# max1k.net
KiCad netlist of a schematic drawn in EAGLE
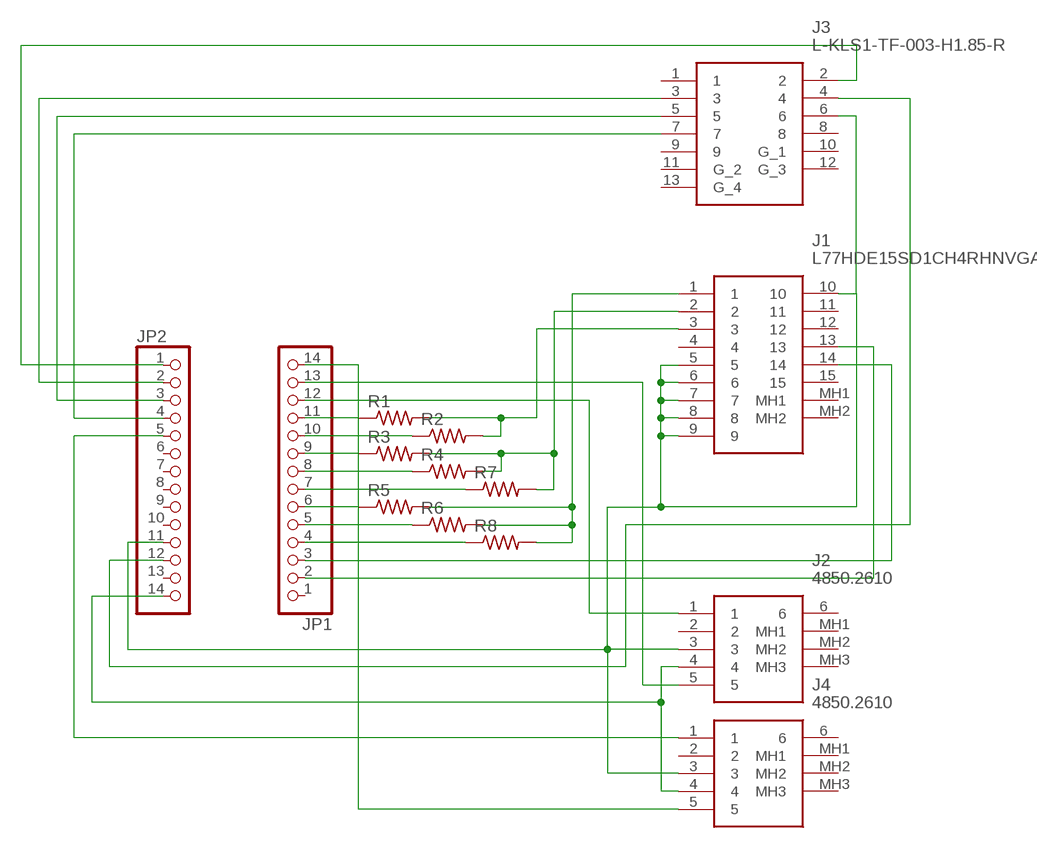
[diagram p0: schematic, sheet 1]

(export (version "E")
  (design (tool "Eeschema 10.0.6"))
  (components
    (comp (ref "J1")
      (value "L77HDE15SD1CH4RHNVGA")
      (footprint "eagle-import:L77HDE15SD1CH4RHNVGA")
      (fields (field (name "MOUSER_PART_NUMBER") "523-7HDE15SDH4RHNVGA"))
      (libsource (lib "eagle-import") (part "L77HDE15SD1CH4RHNVGA"))
    )
    (comp (ref "J2")
      (value "4850.2610")
      (footprint "eagle-import:48502610")
      (fields (field (name "MOUSER_PART_NUMBER") "693-4850.2610"))
      (libsource (lib "eagle-import") (part "4850.2610"))
    )
    (comp (ref "J3")
      (value "L-KLS1-TF-003-H1.85-R")
      (footprint "eagle-import:L-KLS1-TF-003-H1.85-R")
      (libsource (lib "eagle-import") (part "L-KLS1-TF-003-H1.85-R"))
    )
    (comp (ref "J4")
      (value "4850.2610")
      (footprint "eagle-import:48502610")
      (fields (field (name "MOUSER_PART_NUMBER") "693-4850.2610"))
      (libsource (lib "eagle-import") (part "4850.2610"))
    )
    (comp (ref "JP1")
      (value "PINHD-1X14-CB")
      (footprint "eagle-import:1X14-CB")
      (libsource (lib "eagle-import") (part "PINHD-1X14-CB"))
    )
    (comp (ref "JP2")
      (value "PINHD-1X14-CB")
      (footprint "eagle-import:1X14-CB")
      (libsource (lib "eagle-import") (part "PINHD-1X14-CB"))
    )
    (comp (ref "R1")
      (value "R-US_R0805")
      (footprint "eagle-import:R0805")
      (libsource (lib "eagle-import") (part "R-US_R0805"))
    )
    (comp (ref "R2")
      (value "R-US_R0805")
      (footprint "eagle-import:R0805")
      (libsource (lib "eagle-import") (part "R-US_R0805"))
    )
    (comp (ref "R3")
      (value "R-US_R0805")
      (footprint "eagle-import:R0805")
      (libsource (lib "eagle-import") (part "R-US_R0805"))
    )
    (comp (ref "R4")
      (value "R-US_R0805")
      (footprint "eagle-import:R0805")
      (libsource (lib "eagle-import") (part "R-US_R0805"))
    )
    (comp (ref "R5")
      (value "R-US_R0805")
      (footprint "eagle-import:R0805")
      (libsource (lib "eagle-import") (part "R-US_R0805"))
    )
    (comp (ref "R6")
      (value "R-US_R0805")
      (footprint "eagle-import:R0805")
      (libsource (lib "eagle-import") (part "R-US_R0805"))
    )
    (comp (ref "R7")
      (value "R-US_R0805")
      (footprint "eagle-import:R0805")
      (libsource (lib "eagle-import") (part "R-US_R0805"))
    )
    (comp (ref "R8")
      (value "R-US_R0805")
      (footprint "eagle-import:R0805")
      (libsource (lib "eagle-import") (part "R-US_R0805"))
    )
  )
  (nets
    (net (code "1") (name "Net-(J1-Pad1)") (class "Default")
      (node (ref "J1") (pin "1") (pinfunction "1_1") (pintype "bidirectional"))
      (node (ref "R5") (pin "2") (pinfunction "2_2") (pintype "passive"))
      (node (ref "R6") (pin "2") (pinfunction "2_2") (pintype "passive"))
      (node (ref "R8") (pin "2") (pinfunction "2_2") (pintype "passive"))
    )
    (net (code "2") (name "Net-(J1-Pad2)") (class "Default")
      (node (ref "J1") (pin "2") (pinfunction "2_2") (pintype "bidirectional"))
      (node (ref "R3") (pin "2") (pinfunction "2_2") (pintype "passive"))
      (node (ref "R4") (pin "2") (pinfunction "2_2") (pintype "passive"))
      (node (ref "R7") (pin "2") (pinfunction "2_2") (pintype "passive"))
    )
    (net (code "3") (name "Net-(J1-Pad3)") (class "Default")
      (node (ref "J1") (pin "3") (pinfunction "3_3") (pintype "bidirectional"))
      (node (ref "R1") (pin "2") (pinfunction "2_2") (pintype "passive"))
      (node (ref "R2") (pin "2") (pinfunction "2_2") (pintype "passive"))
    )
    (net (code "4") (name "Net-(J1-Pad10)") (class "Default")
      (node (ref "J1") (pin "10") (pinfunction "10_10") (pintype "bidirectional"))
      (node (ref "J1") (pin "5") (pinfunction "5_5") (pintype "bidirectional"))
      (node (ref "J1") (pin "6") (pinfunction "6_6") (pintype "bidirectional"))
      (node (ref "J1") (pin "7") (pinfunction "7_7") (pintype "bidirectional"))
      (node (ref "J1") (pin "8") (pinfunction "8_8") (pintype "bidirectional"))
      (node (ref "J1") (pin "9") (pinfunction "9_9") (pintype "bidirectional"))
      (node (ref "J2") (pin "3") (pinfunction "3_3") (pintype "bidirectional"))
      (node (ref "J3") (pin "6") (pinfunction "6_6") (pintype "bidirectional"))
      (node (ref "J4") (pin "3") (pinfunction "3_3") (pintype "bidirectional"))
      (node (ref "JP2") (pin "11") (pinfunction "11_11") (pintype "passive"))
    )
    (net (code "5") (name "Net-(J1-Pad13)") (class "Default")
      (node (ref "J1") (pin "13") (pinfunction "13_13") (pintype "bidirectional"))
      (node (ref "JP1") (pin "2") (pinfunction "2_2") (pintype "passive"))
    )
    (net (code "6") (name "Net-(J1-Pad14)") (class "Default")
      (node (ref "J1") (pin "14") (pinfunction "14_14") (pintype "bidirectional"))
      (node (ref "JP1") (pin "3") (pinfunction "3_3") (pintype "passive"))
    )
    (net (code "7") (name "Net-(J2-Pad1)") (class "Default")
      (node (ref "J2") (pin "1") (pinfunction "1_1") (pintype "bidirectional"))
      (node (ref "JP1") (pin "12") (pinfunction "12_12") (pintype "passive"))
    )
    (net (code "8") (name "Net-(J2-Pad4)") (class "Default")
      (node (ref "J2") (pin "4") (pinfunction "4_4") (pintype "bidirectional"))
      (node (ref "J4") (pin "4") (pinfunction "4_4") (pintype "bidirectional"))
      (node (ref "JP2") (pin "14") (pinfunction "14_14") (pintype "passive"))
    )
    (net (code "9") (name "Net-(J2-Pad5)") (class "Default")
      (node (ref "J2") (pin "5") (pinfunction "5_5") (pintype "bidirectional"))
      (node (ref "JP1") (pin "13") (pinfunction "13_13") (pintype "passive"))
    )
    (net (code "10") (name "Net-(J3-Pad2)") (class "Default")
      (node (ref "J3") (pin "2") (pinfunction "2_2") (pintype "bidirectional"))
      (node (ref "JP2") (pin "1") (pinfunction "1_1") (pintype "passive"))
    )
    (net (code "11") (name "Net-(J3-Pad3)") (class "Default")
      (node (ref "J3") (pin "3") (pinfunction "3_3") (pintype "bidirectional"))
      (node (ref "JP2") (pin "2") (pinfunction "2_2") (pintype "passive"))
    )
    (net (code "12") (name "Net-(J3-Pad4)") (class "Default")
      (node (ref "J3") (pin "4") (pinfunction "4_4") (pintype "bidirectional"))
      (node (ref "JP2") (pin "12") (pinfunction "12_12") (pintype "passive"))
    )
    (net (code "13") (name "Net-(J3-Pad5)") (class "Default")
      (node (ref "J3") (pin "5") (pinfunction "5_5") (pintype "bidirectional"))
      (node (ref "JP2") (pin "3") (pinfunction "3_3") (pintype "passive"))
    )
    (net (code "14") (name "Net-(J3-Pad7)") (class "Default")
      (node (ref "J3") (pin "7") (pinfunction "7_7") (pintype "bidirectional"))
      (node (ref "JP2") (pin "4") (pinfunction "4_4") (pintype "passive"))
    )
    (net (code "15") (name "Net-(J4-Pad1)") (class "Default")
      (node (ref "J4") (pin "1") (pinfunction "1_1") (pintype "bidirectional"))
      (node (ref "JP2") (pin "5") (pinfunction "5_5") (pintype "passive"))
    )
    (net (code "16") (name "Net-(J4-Pad5)") (class "Default")
      (node (ref "J4") (pin "5") (pinfunction "5_5") (pintype "bidirectional"))
      (node (ref "JP1") (pin "14") (pinfunction "14_14") (pintype "passive"))
    )
    (net (code "17") (name "Net-(JP1-Pad4)") (class "Default")
      (node (ref "JP1") (pin "4") (pinfunction "4_4") (pintype "passive"))
      (node (ref "R8") (pin "1") (pinfunction "1_1") (pintype "passive"))
    )
    (net (code "18") (name "Net-(JP1-Pad5)") (class "Default")
      (node (ref "JP1") (pin "5") (pinfunction "5_5") (pintype "passive"))
      (node (ref "R6") (pin "1") (pinfunction "1_1") (pintype "passive"))
    )
    (net (code "19") (name "Net-(JP1-Pad6)") (class "Default")
      (node (ref "JP1") (pin "6") (pinfunction "6_6") (pintype "passive"))
      (node (ref "R5") (pin "1") (pinfunction "1_1") (pintype "passive"))
    )
    (net (code "20") (name "Net-(JP1-Pad7)") (class "Default")
      (node (ref "JP1") (pin "7") (pinfunction "7_7") (pintype "passive"))
      (node (ref "R7") (pin "1") (pinfunction "1_1") (pintype "passive"))
    )
    (net (code "21") (name "Net-(JP1-Pad8)") (class "Default")
      (node (ref "JP1") (pin "8") (pinfunction "8_8") (pintype "passive"))
      (node (ref "R4") (pin "1") (pinfunction "1_1") (pintype "passive"))
    )
    (net (code "22") (name "Net-(JP1-Pad9)") (class "Default")
      (node (ref "JP1") (pin "9") (pinfunction "9_9") (pintype "passive"))
      (node (ref "R3") (pin "1") (pinfunction "1_1") (pintype "passive"))
    )
    (net (code "23") (name "Net-(JP1-Pad10)") (class "Default")
      (node (ref "JP1") (pin "10") (pinfunction "10_10") (pintype "passive"))
      (node (ref "R2") (pin "1") (pinfunction "1_1") (pintype "passive"))
    )
    (net (code "24") (name "Net-(JP1-Pad11)") (class "Default")
      (node (ref "JP1") (pin "11") (pinfunction "11_11") (pintype "passive"))
      (node (ref "R1") (pin "1") (pinfunction "1_1") (pintype "passive"))
    )
    (net (code "25") (name "unconnected-(J1-Pad4)") (class "Default")
      (node (ref "J1") (pin "4") (pinfunction "4_4") (pintype "bidirectional"))
    )
    (net (code "26") (name "unconnected-(J1-Pad11)") (class "Default")
      (node (ref "J1") (pin "11") (pinfunction "11_11") (pintype "bidirectional"))
    )
    (net (code "27") (name "unconnected-(J1-Pad12)") (class "Default")
      (node (ref "J1") (pin "12") (pinfunction "12_12") (pintype "bidirectional"))
    )
    (net (code "28") (name "unconnected-(J1-Pad15)") (class "Default")
      (node (ref "J1") (pin "15") (pinfunction "15_15") (pintype "bidirectional"))
    )
    (net (code "29") (name "unconnected-(J1-PadMH1)") (class "Default")
      (node (ref "J1") (pin "MH1") (pinfunction "MH1_MH1") (pintype "bidirectional"))
    )
    (net (code "30") (name "unconnected-(J1-PadMH2)") (class "Default")
      (node (ref "J1") (pin "MH2") (pinfunction "MH2_MH2") (pintype "bidirectional"))
    )
    (net (code "31") (name "unconnected-(J2-Pad2)") (class "Default")
      (node (ref "J2") (pin "2") (pinfunction "2_2") (pintype "bidirectional"))
    )
    (net (code "32") (name "unconnected-(J2-Pad6)") (class "Default")
      (node (ref "J2") (pin "6") (pinfunction "6_6") (pintype "bidirectional"))
    )
    (net (code "33") (name "unconnected-(J2-PadMH1)") (class "Default")
      (node (ref "J2") (pin "MH1") (pinfunction "MH1_MH1") (pintype "bidirectional"))
    )
    (net (code "34") (name "unconnected-(J2-PadMH2)") (class "Default")
      (node (ref "J2") (pin "MH2") (pinfunction "MH2_MH2") (pintype "bidirectional"))
    )
    (net (code "35") (name "unconnected-(J2-PadMH3)") (class "Default")
      (node (ref "J2") (pin "MH3") (pinfunction "MH3_MH3") (pintype "bidirectional"))
    )
    (net (code "36") (name "unconnected-(J3-G_1-Pad10)") (class "Default")
      (node (ref "J3") (pin "10") (pinfunction "G_1_10") (pintype "bidirectional"))
    )
    (net (code "37") (name "unconnected-(J3-G_2-Pad11)") (class "Default")
      (node (ref "J3") (pin "11") (pinfunction "G_2_11") (pintype "bidirectional"))
    )
    (net (code "38") (name "unconnected-(J3-G_3-Pad12)") (class "Default")
      (node (ref "J3") (pin "12") (pinfunction "G_3_12") (pintype "bidirectional"))
    )
    (net (code "39") (name "unconnected-(J3-G_4-Pad13)") (class "Default")
      (node (ref "J3") (pin "13") (pinfunction "G_4_13") (pintype "bidirectional"))
    )
    (net (code "40") (name "unconnected-(J3-Pad1)") (class "Default")
      (node (ref "J3") (pin "1") (pinfunction "1_1") (pintype "bidirectional"))
    )
    (net (code "41") (name "unconnected-(J3-Pad8)") (class "Default")
      (node (ref "J3") (pin "8") (pinfunction "8_8") (pintype "bidirectional"))
    )
    (net (code "42") (name "unconnected-(J3-Pad9)") (class "Default")
      (node (ref "J3") (pin "9") (pinfunction "9_9") (pintype "bidirectional"))
    )
    (net (code "43") (name "unconnected-(J4-Pad2)") (class "Default")
      (node (ref "J4") (pin "2") (pinfunction "2_2") (pintype "bidirectional"))
    )
    (net (code "44") (name "unconnected-(J4-Pad6)") (class "Default")
      (node (ref "J4") (pin "6") (pinfunction "6_6") (pintype "bidirectional"))
    )
    (net (code "45") (name "unconnected-(J4-PadMH1)") (class "Default")
      (node (ref "J4") (pin "MH1") (pinfunction "MH1_MH1") (pintype "bidirectional"))
    )
    (net (code "46") (name "unconnected-(J4-PadMH2)") (class "Default")
      (node (ref "J4") (pin "MH2") (pinfunction "MH2_MH2") (pintype "bidirectional"))
    )
    (net (code "47") (name "unconnected-(J4-PadMH3)") (class "Default")
      (node (ref "J4") (pin "MH3") (pinfunction "MH3_MH3") (pintype "bidirectional"))
    )
    (net (code "48") (name "unconnected-(JP1-Pad1)") (class "Default")
      (node (ref "JP1") (pin "1") (pinfunction "1_1") (pintype "passive"))
    )
    (net (code "49") (name "unconnected-(JP2-Pad6)") (class "Default")
      (node (ref "JP2") (pin "6") (pinfunction "6_6") (pintype "passive"))
    )
    (net (code "50") (name "unconnected-(JP2-Pad7)") (class "Default")
      (node (ref "JP2") (pin "7") (pinfunction "7_7") (pintype "passive"))
    )
    (net (code "51") (name "unconnected-(JP2-Pad8)") (class "Default")
      (node (ref "JP2") (pin "8") (pinfunction "8_8") (pintype "passive"))
    )
    (net (code "52") (name "unconnected-(JP2-Pad9)") (class "Default")
      (node (ref "JP2") (pin "9") (pinfunction "9_9") (pintype "passive"))
    )
    (net (code "53") (name "unconnected-(JP2-Pad10)") (class "Default")
      (node (ref "JP2") (pin "10") (pinfunction "10_10") (pintype "passive"))
    )
    (net (code "54") (name "unconnected-(JP2-Pad13)") (class "Default")
      (node (ref "JP2") (pin "13") (pinfunction "13_13") (pintype "passive"))
    )
  )
)
